# Tesis_Driver_TMC2209.net
KiCad netlist of a schematic drawn in Altium Designer
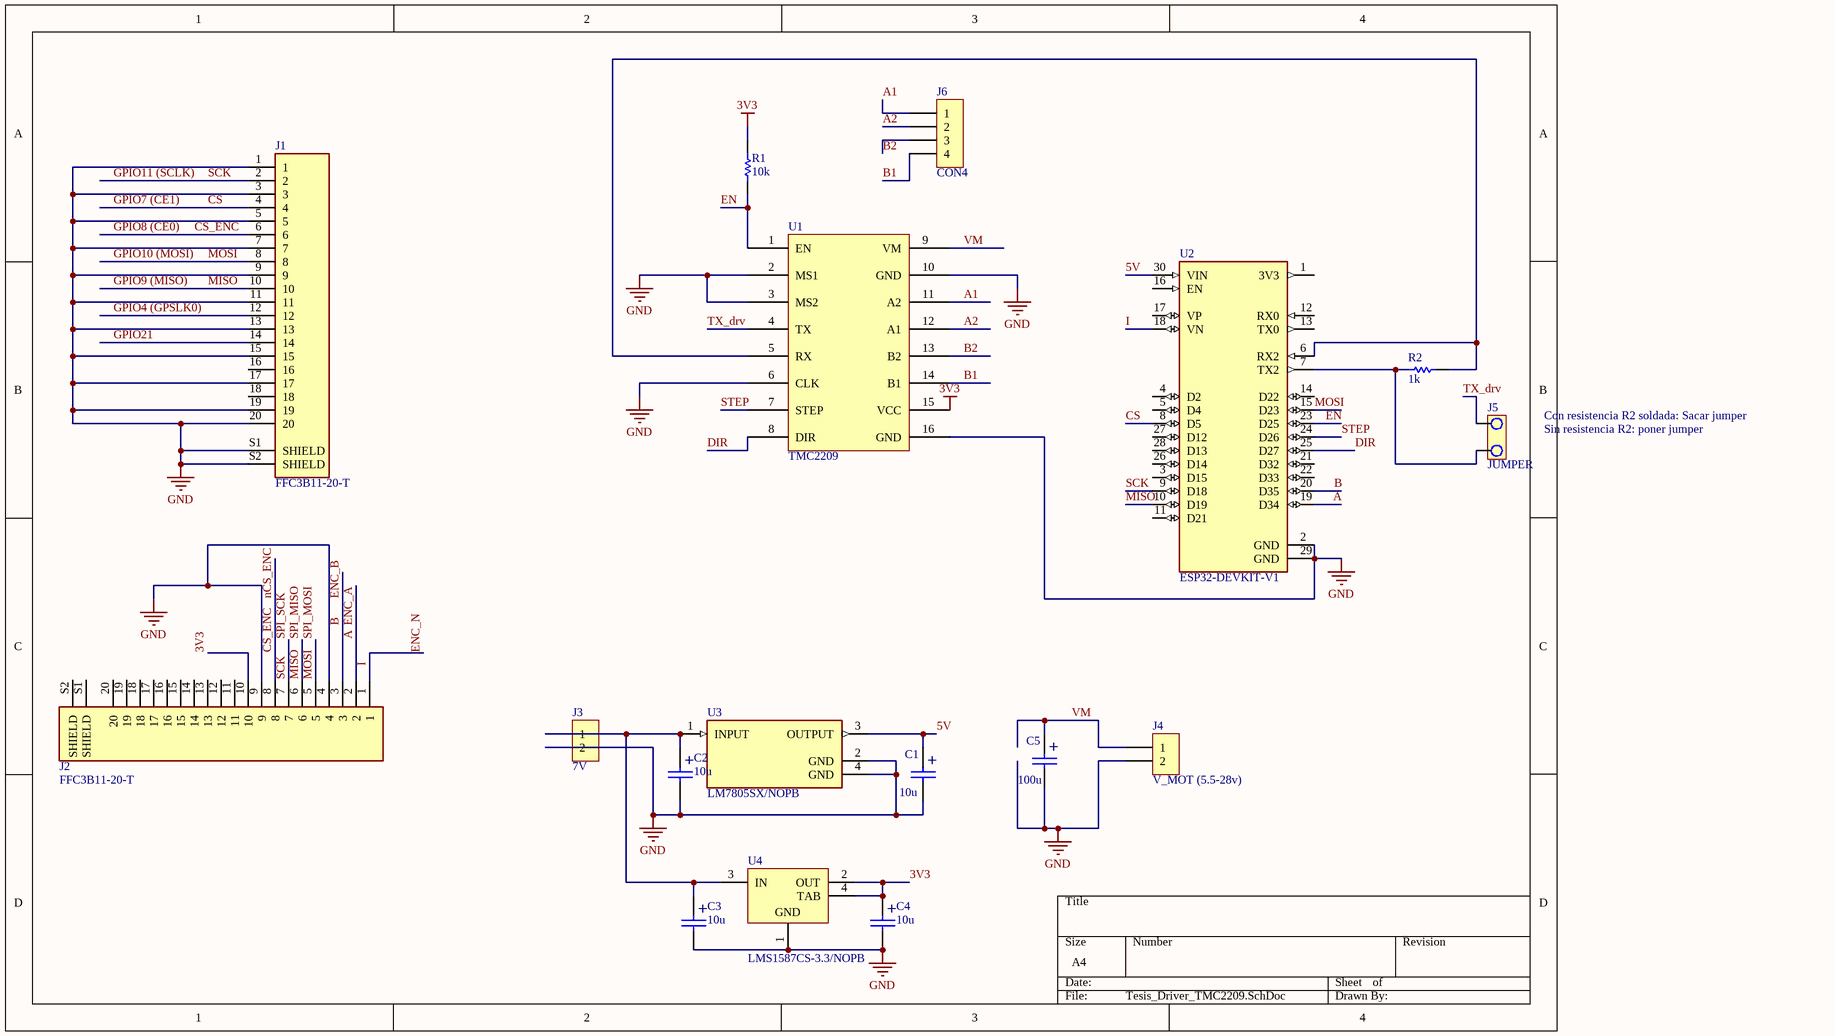
[diagram p0: Tesis_Driver_TMC2209.SchDoc]

(export (version "E")
  (design (tool "Eeschema 10.0.6"))
  (components
    (comp (ref "C1") (value "10u") (footprint "CAP100RP") (libsource (lib "LIBEBAL") (part "CAPPOL")))
    (comp (ref "C2") (value "10u") (footprint "CAP100RP") (libsource (lib "LIBEBAL") (part "CAPPOL")))
    (comp (ref "C3") (value "10u") (footprint "CAP100RP") (libsource (lib "LIBEBAL") (part "CAPPOL")))
    (comp (ref "C4") (value "10u") (footprint "CAP100RP") (libsource (lib "LIBEBAL") (part "CAPPOL")))
    (comp (ref "C5") (value "100u") (footprint "CAP100RP") (libsource (lib "LIB PIO IX") (part "CAPPOL")))
    (comp (ref "J1")
      (value "FFC3B11-20-T")
      (footprint "GCT_FFC3B11-20-T")
      (description "20 Position FFC, FPC Connector Contacts, Top 0.039 (1.00mm) Surface Mount, Right Angle")
      (fields (field (name "MF") "Global Connector Technology"))
      (libsource (lib "") (part "FFC3B11-20-T_1"))
    )
    (comp (ref "J2")
      (value "FFC3B11-20-T")
      (footprint "GCT_FFC3B11-20-T")
      (description "20 Position FFC, FPC Connector Contacts, Top 0.039 (1.00mm) Surface Mount, Right Angle")
      (fields (field (name "MF") "Global Connector Technology"))
      (libsource (lib "Trinamics Drivers") (part "FFC3B11-20-T"))
    )
    (comp (ref "J3")
      (value "7V")
      (footprint "BORNERA2")
      (libsource (lib "Trinamics Drivers") (part "BORNERA 2"))
    )
    (comp (ref "J4")
      (value "V_MOT (5.5-28v)")
      (footprint "BORNERA2")
      (libsource (lib "Trinamics Drivers") (part "BORNERA 2"))
    )
    (comp (ref "J5") (value "JUMPER") (footprint "JUMPER2") (libsource (lib "LIB PIO IX") (part "JUMPER")))
    (comp (ref "J6") (value "CON4") (footprint "SIP4") (libsource (lib "LIB PIO IX") (part "CON4")))
    (comp (ref "R1") (value "10k") (footprint "RES400") (libsource (lib "LIBEBAL") (part "RES")))
    (comp (ref "R2") (value "1k") (footprint "RES400") (libsource (lib "LIBEBAL") (part "RES")))
    (comp (ref "U1")
      (value "TMC2209")
      (footprint "TMC2209")
      (libsource (lib "Trinamics Drivers") (part "TMC2209"))
    )
    (comp (ref "U2")
      (value "ESP32-DEVKIT-V1")
      (footprint "MODULE_ESP32_DEVKIT_V1")
      (fields (field (name "MF") "Do it"))
      (libsource (lib "Trinamics Drivers") (part "ESP32-DEVKIT-V1"))
    )
    (comp (ref "U3")
      (value "LM7805SX/NOPB")
      (footprint "FP-KTT0003B-MFG")
      (description "IC REG LIN 5V 1.5A DDPAK/TO263-3")
      (fields
        (field (name "OCTOPART") "https://octopart.com/lm7805sx%2Fnopb-texas+instruments-74629994")
        (field (name "MANUFACTURER") "Texas Instruments")
      )
      (libsource (lib "Altium Content Vault") (part "bbc5c6f8b1069d3695ea5b916bb48f2"))
    )
    (comp (ref "U4")
      (value "LMS1587CS-3.3/NOPB")
      (footprint "KTT0003B_N")
      (description "3A Low Dropout Fast Response Regulators, 3-pin TO-263, Pb-Free")
      (fields (field (name "MANUFACTURER") "Texas Instruments"))
      (libsource (lib "Altium Content Vault") (part "PM-REG-LM1086-SOT4"))
    )
  )
  (nets
    (net (code "1") (name "/5V") (class "Default")
      (node (ref "C1") (pin "1") (pinfunction "1_1") (pintype "passive"))
      (node (ref "U2") (pin "30") (pinfunction "VIN_30") (pintype "input"))
      (node (ref "U3") (pin "3") (pinfunction "OUTPUT_3") (pintype "output"))
    )
    (net (code "2") (name "/A") (class "Default")
      (node (ref "J2") (pin "2") (pinfunction "2_2") (pintype "passive"))
      (node (ref "U2") (pin "19") (pinfunction "D34_19") (pintype "bidirectional"))
    )
    (net (code "3") (name "/A1") (class "Default")
      (node (ref "J6") (pin "1") (pinfunction "1_1") (pintype "passive"))
      (node (ref "U1") (pin "11") (pinfunction "A2_11") (pintype "passive"))
    )
    (net (code "4") (name "/A2") (class "Default")
      (node (ref "J6") (pin "2") (pinfunction "2_2") (pintype "passive"))
      (node (ref "U1") (pin "12") (pinfunction "A1_12") (pintype "passive"))
    )
    (net (code "5") (name "/B") (class "Default")
      (node (ref "J2") (pin "3") (pinfunction "3_3") (pintype "passive"))
      (node (ref "U2") (pin "20") (pinfunction "D35_20") (pintype "bidirectional"))
    )
    (net (code "6") (name "/B1") (class "Default")
      (node (ref "J6") (pin "4") (pinfunction "4_4") (pintype "passive"))
      (node (ref "U1") (pin "14") (pinfunction "B1_14") (pintype "passive"))
    )
    (net (code "7") (name "/B2") (class "Default")
      (node (ref "J6") (pin "3") (pinfunction "3_3") (pintype "passive"))
      (node (ref "U1") (pin "13") (pinfunction "B2_13") (pintype "passive"))
    )
    (net (code "8") (name "/CS") (class "Default")
      (node (ref "J1") (pin "4") (pinfunction "4_4") (pintype "passive"))
      (node (ref "U2") (pin "8") (pinfunction "D5_8") (pintype "bidirectional"))
    )
    (net (code "9") (name "/CS_ENC") (class "Default")
      (node (ref "J1") (pin "6") (pinfunction "6_6") (pintype "passive"))
      (node (ref "J2") (pin "8") (pinfunction "8_8") (pintype "passive"))
    )
    (net (code "10") (name "/DIR") (class "Default")
      (node (ref "U1") (pin "8") (pinfunction "DIR_8") (pintype "passive"))
      (node (ref "U2") (pin "25") (pinfunction "D27_25") (pintype "bidirectional"))
    )
    (net (code "11") (name "/EN") (class "Default")
      (node (ref "R1") (pin "1") (pinfunction "1_1") (pintype "passive"))
      (node (ref "U1") (pin "1") (pinfunction "EN_1") (pintype "passive"))
      (node (ref "U2") (pin "23") (pinfunction "D25_23") (pintype "bidirectional"))
    )
    (net (code "12") (name "/ENC_N") (class "Default")
      (node (ref "J2") (pin "1") (pinfunction "1_1") (pintype "passive"))
      (node (ref "U2") (pin "18") (pinfunction "VN_18") (pintype "bidirectional"))
    )
    (net (code "13") (name "/GPIO4 (GPSLK0)") (class "Default")
      (node (ref "J1") (pin "12") (pinfunction "12_12") (pintype "passive"))
    )
    (net (code "14") (name "/GPIO9 (MISO)") (class "Default")
      (node (ref "J1") (pin "10") (pinfunction "10_10") (pintype "passive"))
      (node (ref "J2") (pin "6") (pinfunction "6_6") (pintype "passive"))
      (node (ref "U2") (pin "10") (pinfunction "D19_10") (pintype "bidirectional"))
    )
    (net (code "15") (name "/GPIO10 (MOSI)") (class "Default")
      (node (ref "J1") (pin "8") (pinfunction "8_8") (pintype "passive"))
      (node (ref "J2") (pin "5") (pinfunction "5_5") (pintype "passive"))
      (node (ref "U2") (pin "15") (pinfunction "D23_15") (pintype "bidirectional"))
    )
    (net (code "16") (name "/GPIO11 (SCLK)") (class "Default")
      (node (ref "J1") (pin "2") (pinfunction "2_2") (pintype "passive"))
      (node (ref "J2") (pin "7") (pinfunction "7_7") (pintype "passive"))
      (node (ref "U2") (pin "9") (pinfunction "D18_9") (pintype "bidirectional"))
    )
    (net (code "17") (name "/GPIO21") (class "Default")
      (node (ref "J1") (pin "14") (pinfunction "14_14") (pintype "passive"))
    )
    (net (code "18") (name "/STEP") (class "Default")
      (node (ref "U1") (pin "7") (pinfunction "STEP_7") (pintype "passive"))
      (node (ref "U2") (pin "24") (pinfunction "D26_24") (pintype "bidirectional"))
    )
    (net (code "19") (name "/TX_drv") (class "Default")
      (node (ref "J5") (pin "2") (pinfunction "2_2") (pintype "passive"))
      (node (ref "U1") (pin "4") (pinfunction "TX_4") (pintype "passive"))
    )
    (net (code "20") (name "/VM") (class "Default")
      (node (ref "C5") (pin "1") (pinfunction "1_1") (pintype "passive"))
      (node (ref "J4") (pin "1") (pinfunction "1_1") (pintype "passive"))
      (node (ref "U1") (pin "9") (pinfunction "VM_9") (pintype "passive"))
    )
    (net (code "21") (name "3V3") (class "Default")
      (node (ref "C4") (pin "1") (pinfunction "1_1") (pintype "passive"))
      (node (ref "J2") (pin "10") (pinfunction "10_10") (pintype "passive"))
      (node (ref "R1") (pin "2") (pinfunction "2_2") (pintype "passive"))
      (node (ref "U1") (pin "15") (pinfunction "VCC_15") (pintype "passive"))
      (node (ref "U4") (pin "2") (pinfunction "OUT_2") (pintype "power_in"))
      (node (ref "U4") (pin "4") (pinfunction "TAB_4") (pintype "power_in"))
    )
    (net (code "22") (name "GND") (class "Default")
      (node (ref "C1") (pin "2") (pinfunction "2_2") (pintype "passive"))
      (node (ref "C2") (pin "2") (pinfunction "2_2") (pintype "passive"))
      (node (ref "C3") (pin "2") (pinfunction "2_2") (pintype "passive"))
      (node (ref "C4") (pin "2") (pinfunction "2_2") (pintype "passive"))
      (node (ref "C5") (pin "2") (pinfunction "2_2") (pintype "passive"))
      (node (ref "J1") (pin "1") (pinfunction "1_1") (pintype "passive"))
      (node (ref "J1") (pin "11") (pinfunction "11_11") (pintype "passive"))
      (node (ref "J1") (pin "13") (pinfunction "13_13") (pintype "passive"))
      (node (ref "J1") (pin "15") (pinfunction "15_15") (pintype "passive"))
      (node (ref "J1") (pin "17") (pinfunction "17_17") (pintype "passive"))
      (node (ref "J1") (pin "19") (pinfunction "19_19") (pintype "passive"))
      (node (ref "J1") (pin "20") (pinfunction "20_20") (pintype "passive"))
      (node (ref "J1") (pin "3") (pinfunction "3_3") (pintype "passive"))
      (node (ref "J1") (pin "5") (pinfunction "5_5") (pintype "passive"))
      (node (ref "J1") (pin "7") (pinfunction "7_7") (pintype "passive"))
      (node (ref "J1") (pin "9") (pinfunction "9_9") (pintype "passive"))
      (node (ref "J1") (pin "S1") (pinfunction "SHIELD_S1") (pintype "passive"))
      (node (ref "J1") (pin "S2") (pinfunction "SHIELD_S2") (pintype "passive"))
      (node (ref "J2") (pin "4") (pinfunction "4_4") (pintype "passive"))
      (node (ref "J2") (pin "9") (pinfunction "9_9") (pintype "passive"))
      (node (ref "J3") (pin "2") (pinfunction "2_2") (pintype "passive"))
      (node (ref "J4") (pin "2") (pinfunction "2_2") (pintype "passive"))
      (node (ref "U1") (pin "10") (pinfunction "GND_10") (pintype "passive"))
      (node (ref "U1") (pin "16") (pinfunction "GND_16") (pintype "passive"))
      (node (ref "U1") (pin "2") (pinfunction "MS1_2") (pintype "passive"))
      (node (ref "U1") (pin "3") (pinfunction "MS2_3") (pintype "passive"))
      (node (ref "U1") (pin "6") (pinfunction "CLK_6") (pintype "passive"))
      (node (ref "U2") (pin "2") (pinfunction "GND_2") (pintype "power_in"))
      (node (ref "U2") (pin "29") (pinfunction "GND_29") (pintype "power_in"))
      (node (ref "U3") (pin "2") (pinfunction "GND_2") (pintype "power_in"))
      (node (ref "U3") (pin "4") (pinfunction "GND_4") (pintype "power_in"))
      (node (ref "U4") (pin "1") (pinfunction "GND_1") (pintype "power_in"))
    )
    (net (code "23") (name "Net-(U1-RX)") (class "Default")
      (node (ref "R2") (pin "1") (pinfunction "1_1") (pintype "passive"))
      (node (ref "U1") (pin "5") (pinfunction "RX_5") (pintype "passive"))
      (node (ref "U2") (pin "6") (pinfunction "RX2_6") (pintype "input"))
    )
    (net (code "24") (name "Net-(U2-TX2)") (class "Default")
      (node (ref "J5") (pin "1") (pinfunction "1_1") (pintype "passive"))
      (node (ref "R2") (pin "2") (pinfunction "2_2") (pintype "passive"))
      (node (ref "U2") (pin "7") (pinfunction "TX2_7") (pintype "output"))
    )
    (net (code "25") (name "Net-(U3-INPUT)") (class "Default")
      (node (ref "C2") (pin "1") (pinfunction "1_1") (pintype "passive"))
      (node (ref "C3") (pin "1") (pinfunction "1_1") (pintype "passive"))
      (node (ref "J3") (pin "1") (pinfunction "1_1") (pintype "passive"))
      (node (ref "U3") (pin "1") (pinfunction "INPUT_1") (pintype "input"))
      (node (ref "U4") (pin "3") (pinfunction "IN_3") (pintype "power_in"))
    )
    (net (code "26") (name "unconnected-(J1-Pad16)") (class "Default")
      (node (ref "J1") (pin "16") (pinfunction "16_16") (pintype "passive"))
    )
    (net (code "27") (name "unconnected-(J1-Pad18)") (class "Default")
      (node (ref "J1") (pin "18") (pinfunction "18_18") (pintype "passive"))
    )
    (net (code "28") (name "unconnected-(J2-Pad11)") (class "Default")
      (node (ref "J2") (pin "11") (pinfunction "11_11") (pintype "passive"))
    )
    (net (code "29") (name "unconnected-(J2-Pad12)") (class "Default")
      (node (ref "J2") (pin "12") (pinfunction "12_12") (pintype "passive"))
    )
    (net (code "30") (name "unconnected-(J2-Pad13)") (class "Default")
      (node (ref "J2") (pin "13") (pinfunction "13_13") (pintype "passive"))
    )
    (net (code "31") (name "unconnected-(J2-Pad14)") (class "Default")
      (node (ref "J2") (pin "14") (pinfunction "14_14") (pintype "passive"))
    )
    (net (code "32") (name "unconnected-(J2-Pad15)") (class "Default")
      (node (ref "J2") (pin "15") (pinfunction "15_15") (pintype "passive"))
    )
    (net (code "33") (name "unconnected-(J2-Pad16)") (class "Default")
      (node (ref "J2") (pin "16") (pinfunction "16_16") (pintype "passive"))
    )
    (net (code "34") (name "unconnected-(J2-Pad17)") (class "Default")
      (node (ref "J2") (pin "17") (pinfunction "17_17") (pintype "passive"))
    )
    (net (code "35") (name "unconnected-(J2-Pad18)") (class "Default")
      (node (ref "J2") (pin "18") (pinfunction "18_18") (pintype "passive"))
    )
    (net (code "36") (name "unconnected-(J2-Pad19)") (class "Default")
      (node (ref "J2") (pin "19") (pinfunction "19_19") (pintype "passive"))
    )
    (net (code "37") (name "unconnected-(J2-Pad20)") (class "Default")
      (node (ref "J2") (pin "20") (pinfunction "20_20") (pintype "passive"))
    )
    (net (code "38") (name "unconnected-(J2-SHIELD-PadS1)") (class "Default")
      (node (ref "J2") (pin "S1") (pinfunction "SHIELD_S1") (pintype "passive"))
    )
    (net (code "39") (name "unconnected-(J2-SHIELD-PadS2)") (class "Default")
      (node (ref "J2") (pin "S2") (pinfunction "SHIELD_S2") (pintype "passive"))
    )
    (net (code "40") (name "unconnected-(U2-3V3-Pad1)") (class "Default")
      (node (ref "U2") (pin "1") (pinfunction "3V3_1") (pintype "output"))
    )
    (net (code "41") (name "unconnected-(U2-D2-Pad4)") (class "Default")
      (node (ref "U2") (pin "4") (pinfunction "D2_4") (pintype "bidirectional"))
    )
    (net (code "42") (name "unconnected-(U2-D4-Pad5)") (class "Default")
      (node (ref "U2") (pin "5") (pinfunction "D4_5") (pintype "bidirectional"))
    )
    (net (code "43") (name "unconnected-(U2-D12-Pad27)") (class "Default")
      (node (ref "U2") (pin "27") (pinfunction "D12_27") (pintype "bidirectional"))
    )
    (net (code "44") (name "unconnected-(U2-D13-Pad28)") (class "Default")
      (node (ref "U2") (pin "28") (pinfunction "D13_28") (pintype "bidirectional"))
    )
    (net (code "45") (name "unconnected-(U2-D14-Pad26)") (class "Default")
      (node (ref "U2") (pin "26") (pinfunction "D14_26") (pintype "bidirectional"))
    )
    (net (code "46") (name "unconnected-(U2-D15-Pad3)") (class "Default")
      (node (ref "U2") (pin "3") (pinfunction "D15_3") (pintype "bidirectional"))
    )
    (net (code "47") (name "unconnected-(U2-D21-Pad11)") (class "Default")
      (node (ref "U2") (pin "11") (pinfunction "D21_11") (pintype "bidirectional"))
    )
    (net (code "48") (name "unconnected-(U2-D22-Pad14)") (class "Default")
      (node (ref "U2") (pin "14") (pinfunction "D22_14") (pintype "bidirectional"))
    )
    (net (code "49") (name "unconnected-(U2-D32-Pad21)") (class "Default")
      (node (ref "U2") (pin "21") (pinfunction "D32_21") (pintype "bidirectional"))
    )
    (net (code "50") (name "unconnected-(U2-D33-Pad22)") (class "Default")
      (node (ref "U2") (pin "22") (pinfunction "D33_22") (pintype "bidirectional"))
    )
    (net (code "51") (name "unconnected-(U2-EN-Pad16)") (class "Default")
      (node (ref "U2") (pin "16") (pinfunction "EN_16") (pintype "input"))
    )
    (net (code "52") (name "unconnected-(U2-RX0-Pad12)") (class "Default")
      (node (ref "U2") (pin "12") (pinfunction "RX0_12") (pintype "input"))
    )
    (net (code "53") (name "unconnected-(U2-TX0-Pad13)") (class "Default")
      (node (ref "U2") (pin "13") (pinfunction "TX0_13") (pintype "output"))
    )
    (net (code "54") (name "unconnected-(U2-VP-Pad17)") (class "Default")
      (node (ref "U2") (pin "17") (pinfunction "VP_17") (pintype "bidirectional"))
    )
  )
)
